# ElectromagnetArray_V01.net
KiCad netlist of a schematic drawn in EAGLE
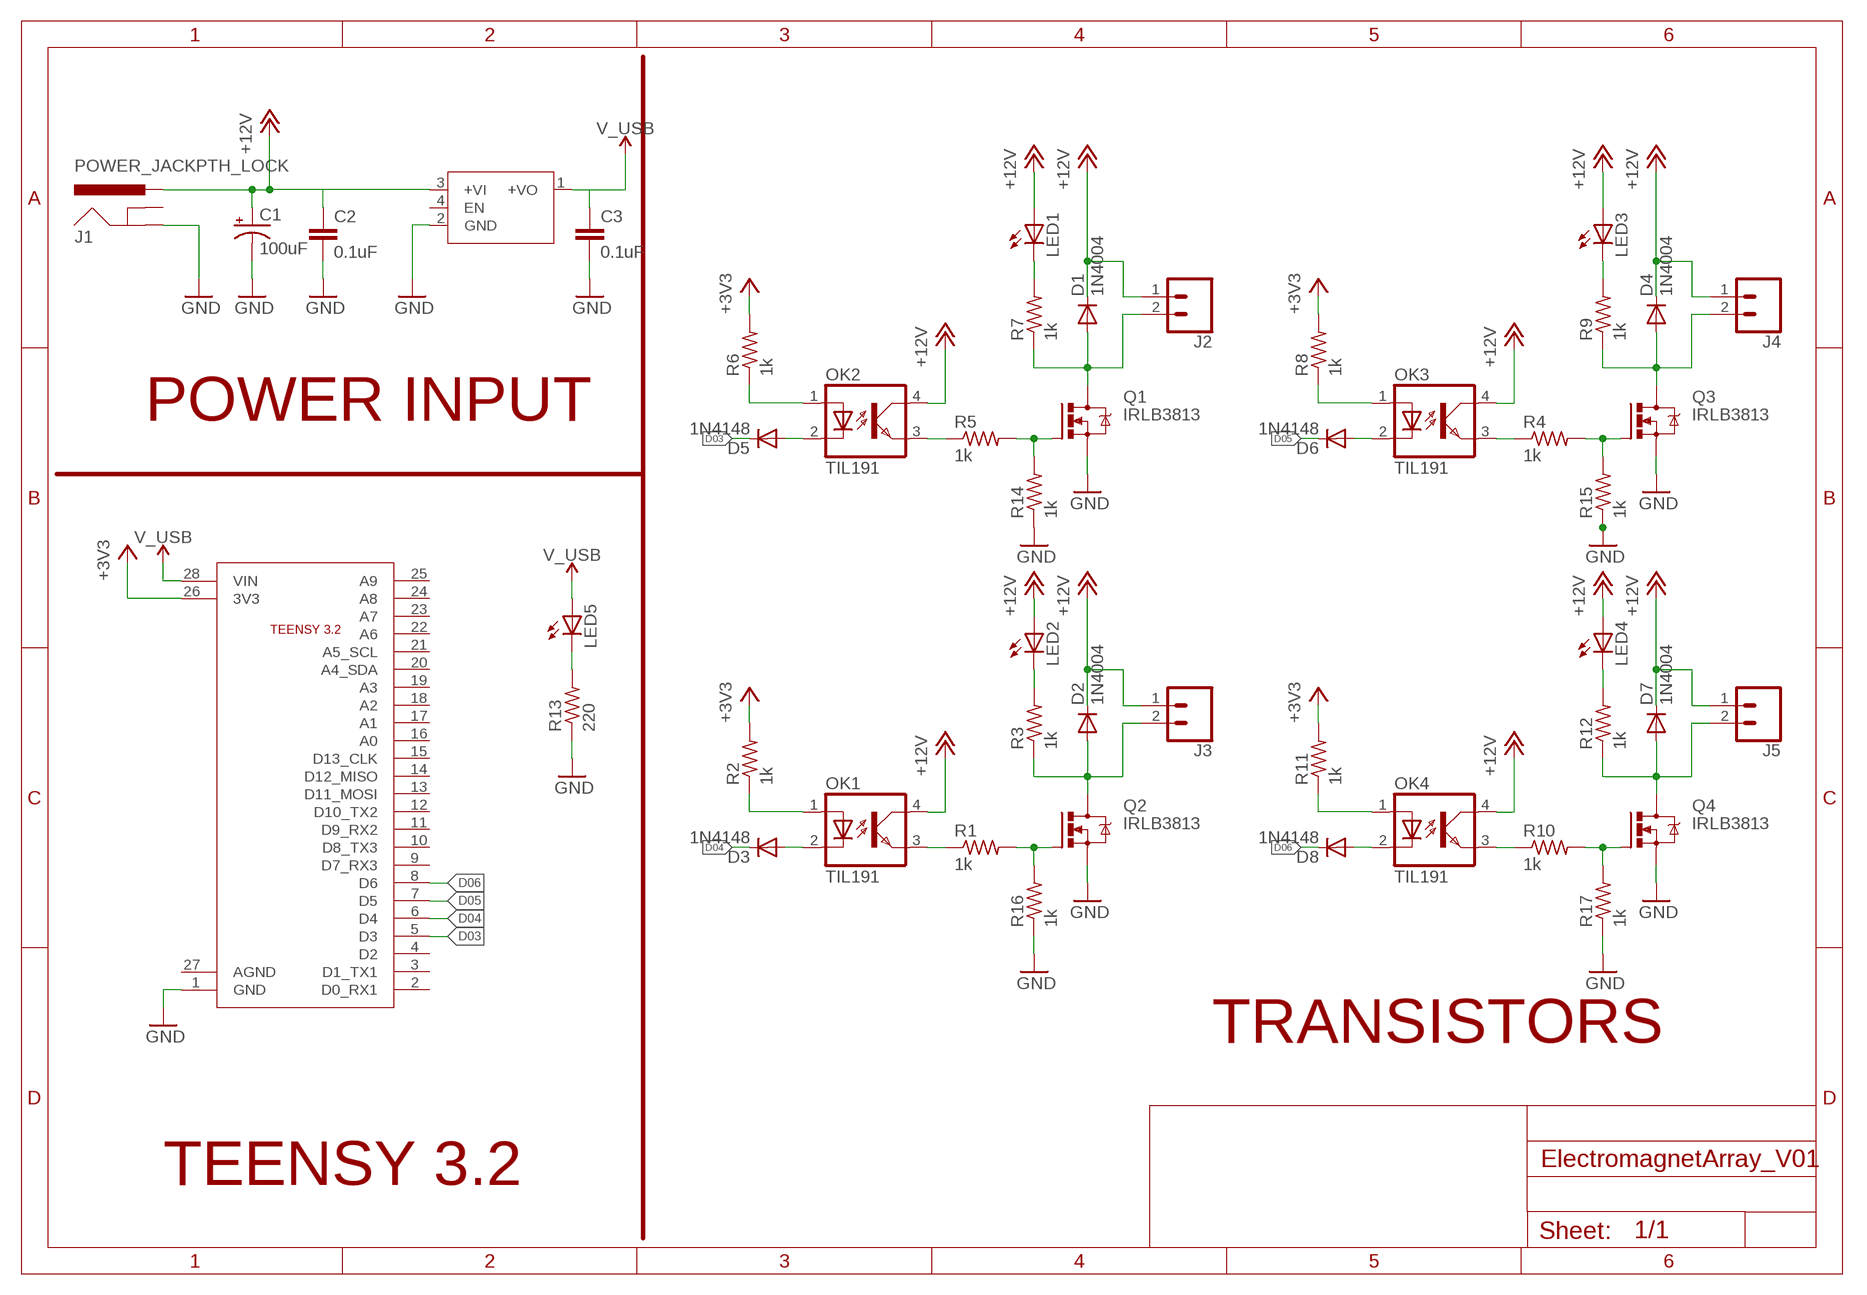
[diagram p0: schematic, sheet 1]

(export (version "E")
  (design (tool "Eeschema 10.0.6"))
  (components
    (comp (ref "C1")
      (value "100uF")
      (footprint "eagle-import:E3,5-8")
      (libsource (lib "eagle-import") (part "CPOL-USE3.5-8"))
    )
    (comp (ref "C2")
      (value "0.1uF")
      (footprint "eagle-import:C050-025X075")
      (libsource (lib "eagle-import") (part "C-EU050-025X075"))
    )
    (comp (ref "C3")
      (value "0.1uF")
      (footprint "eagle-import:C050-025X075")
      (libsource (lib "eagle-import") (part "C-EU050-025X075"))
    )
    (comp (ref "D1")
      (value "1N4004")
      (footprint "eagle-import:DO41-10")
      (libsource (lib "eagle-import") (part "1N4004"))
    )
    (comp (ref "D2")
      (value "1N4004")
      (footprint "eagle-import:DO41-10")
      (libsource (lib "eagle-import") (part "1N4004"))
    )
    (comp (ref "D3")
      (value "1N4148")
      (footprint "eagle-import:DO35-10")
      (libsource (lib "eagle-import") (part "1N4148DO35-10"))
    )
    (comp (ref "D4")
      (value "1N4004")
      (footprint "eagle-import:DO41-10")
      (libsource (lib "eagle-import") (part "1N4004"))
    )
    (comp (ref "D5")
      (value "1N4148")
      (footprint "eagle-import:DO35-10")
      (libsource (lib "eagle-import") (part "1N4148DO35-10"))
    )
    (comp (ref "D6")
      (value "1N4148")
      (footprint "eagle-import:DO35-10")
      (libsource (lib "eagle-import") (part "1N4148DO35-10"))
    )
    (comp (ref "D7")
      (value "1N4004")
      (footprint "eagle-import:DO41-10")
      (libsource (lib "eagle-import") (part "1N4004"))
    )
    (comp (ref "D8")
      (value "1N4148")
      (footprint "eagle-import:DO35-10")
      (libsource (lib "eagle-import") (part "1N4148DO35-10"))
    )
    (comp (ref "J1")
      (value "POWER_JACKPTH_LOCK")
      (footprint "eagle-import:POWER_JACK_PTH_LOCK")
      (libsource (lib "eagle-import") (part "POWER_JACKPTH_LOCK"))
    )
    (comp (ref "J2")
      (value "CONN_025MM")
      (footprint "eagle-import:SCREWTERMINAL-5MM-2")
      (libsource (lib "eagle-import") (part "CONN_025MM"))
    )
    (comp (ref "J3")
      (value "CONN_025MM")
      (footprint "eagle-import:SCREWTERMINAL-5MM-2")
      (libsource (lib "eagle-import") (part "CONN_025MM"))
    )
    (comp (ref "J4")
      (value "CONN_025MM")
      (footprint "eagle-import:SCREWTERMINAL-5MM-2")
      (libsource (lib "eagle-import") (part "CONN_025MM"))
    )
    (comp (ref "J5")
      (value "CONN_025MM")
      (footprint "eagle-import:SCREWTERMINAL-5MM-2")
      (libsource (lib "eagle-import") (part "CONN_025MM"))
    )
    (comp (ref "LED1")
      (value "LED5MM")
      (footprint "eagle-import:LED5MM")
      (libsource (lib "eagle-import") (part "LED5MM"))
    )
    (comp (ref "LED2")
      (value "LED5MM")
      (footprint "eagle-import:LED5MM")
      (libsource (lib "eagle-import") (part "LED5MM"))
    )
    (comp (ref "LED3")
      (value "LED5MM")
      (footprint "eagle-import:LED5MM")
      (libsource (lib "eagle-import") (part "LED5MM"))
    )
    (comp (ref "LED4")
      (value "LED5MM")
      (footprint "eagle-import:LED5MM")
      (libsource (lib "eagle-import") (part "LED5MM"))
    )
    (comp (ref "LED5")
      (value "LED5MM")
      (footprint "eagle-import:LED5MM")
      (libsource (lib "eagle-import") (part "LED5MM"))
    )
    (comp (ref "OK1")
      (value "TIL191")
      (footprint "eagle-import:DIL04")
      (libsource (lib "eagle-import") (part "TIL191"))
    )
    (comp (ref "OK2")
      (value "TIL191")
      (footprint "eagle-import:DIL04")
      (libsource (lib "eagle-import") (part "TIL191"))
    )
    (comp (ref "OK3")
      (value "TIL191")
      (footprint "eagle-import:DIL04")
      (libsource (lib "eagle-import") (part "TIL191"))
    )
    (comp (ref "OK4")
      (value "TIL191")
      (footprint "eagle-import:DIL04")
      (libsource (lib "eagle-import") (part "TIL191"))
    )
    (comp (ref "Q1")
      (value "IRLB3813")
      (footprint "eagle-import:TO220BV")
      (libsource (lib "eagle-import") (part "IRF740"))
    )
    (comp (ref "Q2")
      (value "IRLB3813")
      (footprint "eagle-import:TO220BV")
      (libsource (lib "eagle-import") (part "IRF740"))
    )
    (comp (ref "Q3")
      (value "IRLB3813")
      (footprint "eagle-import:TO220BV")
      (libsource (lib "eagle-import") (part "IRF740"))
    )
    (comp (ref "Q4")
      (value "IRLB3813")
      (footprint "eagle-import:TO220BV")
      (libsource (lib "eagle-import") (part "IRF740"))
    )
    (comp (ref "R1")
      (value "1k")
      (footprint "eagle-import:0204_7")
      (libsource (lib "eagle-import") (part "R-US_0204/7"))
    )
    (comp (ref "R2")
      (value "1k")
      (footprint "eagle-import:0204_7")
      (libsource (lib "eagle-import") (part "R-US_0204/7"))
    )
    (comp (ref "R3")
      (value "1k")
      (footprint "eagle-import:0204_7")
      (libsource (lib "eagle-import") (part "R-US_0204/7"))
    )
    (comp (ref "R4")
      (value "1k")
      (footprint "eagle-import:0204_7")
      (libsource (lib "eagle-import") (part "R-US_0204/7"))
    )
    (comp (ref "R5")
      (value "1k")
      (footprint "eagle-import:0204_7")
      (libsource (lib "eagle-import") (part "R-US_0204/7"))
    )
    (comp (ref "R6")
      (value "1k")
      (footprint "eagle-import:0204_7")
      (libsource (lib "eagle-import") (part "R-US_0204/7"))
    )
    (comp (ref "R7")
      (value "1k")
      (footprint "eagle-import:0204_7")
      (libsource (lib "eagle-import") (part "R-US_0204/7"))
    )
    (comp (ref "R8")
      (value "1k")
      (footprint "eagle-import:0204_7")
      (libsource (lib "eagle-import") (part "R-US_0204/7"))
    )
    (comp (ref "R9")
      (value "1k")
      (footprint "eagle-import:0204_7")
      (libsource (lib "eagle-import") (part "R-US_0204/7"))
    )
    (comp (ref "R10")
      (value "1k")
      (footprint "eagle-import:0204_7")
      (libsource (lib "eagle-import") (part "R-US_0204/7"))
    )
    (comp (ref "R11")
      (value "1k")
      (footprint "eagle-import:0204_7")
      (libsource (lib "eagle-import") (part "R-US_0204/7"))
    )
    (comp (ref "R12")
      (value "1k")
      (footprint "eagle-import:0204_7")
      (libsource (lib "eagle-import") (part "R-US_0204/7"))
    )
    (comp (ref "R13")
      (value "220")
      (footprint "eagle-import:0204_7")
      (libsource (lib "eagle-import") (part "R-US_0204/7"))
    )
    (comp (ref "R14")
      (value "1k")
      (footprint "eagle-import:0204_7")
      (libsource (lib "eagle-import") (part "R-US_0204/7"))
    )
    (comp (ref "R15")
      (value "1k")
      (footprint "eagle-import:0204_7")
      (libsource (lib "eagle-import") (part "R-US_0204/7"))
    )
    (comp (ref "R16")
      (value "1k")
      (footprint "eagle-import:0204_7")
      (libsource (lib "eagle-import") (part "R-US_0204/7"))
    )
    (comp (ref "R17")
      (value "1k")
      (footprint "eagle-import:0204_7")
      (libsource (lib "eagle-import") (part "R-US_0204/7"))
    )
    (comp (ref "U$1")
      (value "TEENSY3.2")
      (footprint "eagle-import:TEENSY")
      (libsource (lib "eagle-import") (part "TEENSY3.2"))
    )
    (comp (ref "U$2")
      (value "SMPS_SMALL")
      (footprint "eagle-import:SMPS_SMALL")
      (libsource (lib "eagle-import") (part "SMPS_SMALL"))
    )
  )
  (nets
    (net (code "1") (name "+3V3") (class "Default")
      (node (ref "R11") (pin "2") (pinfunction "2_2") (pintype "passive"))
      (node (ref "R2") (pin "2") (pinfunction "2_2") (pintype "passive"))
      (node (ref "R6") (pin "2") (pinfunction "2_2") (pintype "passive"))
      (node (ref "R8") (pin "2") (pinfunction "2_2") (pintype "passive"))
      (node (ref "U$1") (pin "26") (pinfunction "3V3_26") (pintype "bidirectional"))
    )
    (net (code "2") (name "+12V") (class "Default")
      (node (ref "C1") (pin "+") (pinfunction "+_+") (pintype "passive"))
      (node (ref "C2") (pin "1") (pinfunction "1_1") (pintype "passive"))
      (node (ref "D1") (pin "C") (pinfunction "C_C") (pintype "passive"))
      (node (ref "D2") (pin "C") (pinfunction "C_C") (pintype "passive"))
      (node (ref "D4") (pin "C") (pinfunction "C_C") (pintype "passive"))
      (node (ref "D7") (pin "C") (pinfunction "C_C") (pintype "passive"))
      (node (ref "J1") (pin "PWR") (pinfunction "PWR_PWR") (pintype "bidirectional"))
      (node (ref "J2") (pin "1") (pinfunction "1_1") (pintype "passive"))
      (node (ref "J3") (pin "1") (pinfunction "1_1") (pintype "passive"))
      (node (ref "J4") (pin "1") (pinfunction "1_1") (pintype "passive"))
      (node (ref "J5") (pin "1") (pinfunction "1_1") (pintype "passive"))
      (node (ref "LED1") (pin "A") (pinfunction "A_A") (pintype "passive"))
      (node (ref "LED2") (pin "A") (pinfunction "A_A") (pintype "passive"))
      (node (ref "LED3") (pin "A") (pinfunction "A_A") (pintype "passive"))
      (node (ref "LED4") (pin "A") (pinfunction "A_A") (pintype "passive"))
      (node (ref "OK1") (pin "4") (pinfunction "COL_4") (pintype "passive"))
      (node (ref "OK2") (pin "4") (pinfunction "COL_4") (pintype "passive"))
      (node (ref "OK3") (pin "4") (pinfunction "COL_4") (pintype "passive"))
      (node (ref "OK4") (pin "4") (pinfunction "COL_4") (pintype "passive"))
      (node (ref "U$2") (pin "3") (pinfunction "+VI_3") (pintype "bidirectional"))
    )
    (net (code "3") (name "D03") (class "Default")
      (node (ref "D5") (pin "C") (pinfunction "C_C") (pintype "passive"))
      (node (ref "U$1") (pin "5") (pinfunction "D3_5") (pintype "bidirectional"))
    )
    (net (code "4") (name "D04") (class "Default")
      (node (ref "D3") (pin "C") (pinfunction "C_C") (pintype "passive"))
      (node (ref "U$1") (pin "6") (pinfunction "D4_6") (pintype "bidirectional"))
    )
    (net (code "5") (name "D05") (class "Default")
      (node (ref "D6") (pin "C") (pinfunction "C_C") (pintype "passive"))
      (node (ref "U$1") (pin "7") (pinfunction "D5_7") (pintype "bidirectional"))
    )
    (net (code "6") (name "D06") (class "Default")
      (node (ref "D8") (pin "C") (pinfunction "C_C") (pintype "passive"))
      (node (ref "U$1") (pin "8") (pinfunction "D6_8") (pintype "bidirectional"))
    )
    (net (code "7") (name "GND") (class "Default")
      (node (ref "C1") (pin "-") (pinfunction "-_-") (pintype "passive"))
      (node (ref "C2") (pin "2") (pinfunction "2_2") (pintype "passive"))
      (node (ref "C3") (pin "2") (pinfunction "2_2") (pintype "passive"))
      (node (ref "J1") (pin "GND") (pinfunction "GND_GND") (pintype "bidirectional"))
      (node (ref "Q1") (pin "S") (pinfunction "S_S") (pintype "passive"))
      (node (ref "Q2") (pin "S") (pinfunction "S_S") (pintype "passive"))
      (node (ref "Q3") (pin "S") (pinfunction "S_S") (pintype "passive"))
      (node (ref "Q4") (pin "S") (pinfunction "S_S") (pintype "passive"))
      (node (ref "R13") (pin "1") (pinfunction "1_1") (pintype "passive"))
      (node (ref "R14") (pin "1") (pinfunction "1_1") (pintype "passive"))
      (node (ref "R15") (pin "1") (pinfunction "1_1") (pintype "passive"))
      (node (ref "R16") (pin "1") (pinfunction "1_1") (pintype "passive"))
      (node (ref "R17") (pin "1") (pinfunction "1_1") (pintype "passive"))
      (node (ref "U$1") (pin "1") (pinfunction "GND_1") (pintype "bidirectional"))
      (node (ref "U$2") (pin "2") (pinfunction "GND_2") (pintype "bidirectional"))
    )
    (net (code "8") (name "Net-(D1-PadA)") (class "Default")
      (node (ref "D1") (pin "A") (pinfunction "A_A") (pintype "passive"))
      (node (ref "J2") (pin "2") (pinfunction "2_2") (pintype "passive"))
      (node (ref "Q1") (pin "D") (pinfunction "D_D") (pintype "passive"))
      (node (ref "R7") (pin "1") (pinfunction "1_1") (pintype "passive"))
    )
    (net (code "9") (name "Net-(D2-PadA)") (class "Default")
      (node (ref "D2") (pin "A") (pinfunction "A_A") (pintype "passive"))
      (node (ref "J3") (pin "2") (pinfunction "2_2") (pintype "passive"))
      (node (ref "Q2") (pin "D") (pinfunction "D_D") (pintype "passive"))
      (node (ref "R3") (pin "1") (pinfunction "1_1") (pintype "passive"))
    )
    (net (code "10") (name "Net-(D4-PadA)") (class "Default")
      (node (ref "D4") (pin "A") (pinfunction "A_A") (pintype "passive"))
      (node (ref "J4") (pin "2") (pinfunction "2_2") (pintype "passive"))
      (node (ref "Q3") (pin "D") (pinfunction "D_D") (pintype "passive"))
      (node (ref "R9") (pin "1") (pinfunction "1_1") (pintype "passive"))
    )
    (net (code "11") (name "Net-(D7-PadA)") (class "Default")
      (node (ref "D7") (pin "A") (pinfunction "A_A") (pintype "passive"))
      (node (ref "J5") (pin "2") (pinfunction "2_2") (pintype "passive"))
      (node (ref "Q4") (pin "D") (pinfunction "D_D") (pintype "passive"))
      (node (ref "R12") (pin "1") (pinfunction "1_1") (pintype "passive"))
    )
    (net (code "12") (name "Net-(LED1-C)") (class "Default")
      (node (ref "LED1") (pin "K") (pinfunction "C_K") (pintype "passive"))
      (node (ref "R7") (pin "2") (pinfunction "2_2") (pintype "passive"))
    )
    (net (code "13") (name "Net-(LED2-C)") (class "Default")
      (node (ref "LED2") (pin "K") (pinfunction "C_K") (pintype "passive"))
      (node (ref "R3") (pin "2") (pinfunction "2_2") (pintype "passive"))
    )
    (net (code "14") (name "Net-(LED3-C)") (class "Default")
      (node (ref "LED3") (pin "K") (pinfunction "C_K") (pintype "passive"))
      (node (ref "R9") (pin "2") (pinfunction "2_2") (pintype "passive"))
    )
    (net (code "15") (name "Net-(LED4-C)") (class "Default")
      (node (ref "LED4") (pin "K") (pinfunction "C_K") (pintype "passive"))
      (node (ref "R12") (pin "2") (pinfunction "2_2") (pintype "passive"))
    )
    (net (code "16") (name "Net-(LED5-C)") (class "Default")
      (node (ref "LED5") (pin "K") (pinfunction "C_K") (pintype "passive"))
      (node (ref "R13") (pin "2") (pinfunction "2_2") (pintype "passive"))
    )
    (net (code "17") (name "Net-(OK1-A)") (class "Default")
      (node (ref "OK1") (pin "1") (pinfunction "A_1") (pintype "passive"))
      (node (ref "R2") (pin "1") (pinfunction "1_1") (pintype "passive"))
    )
    (net (code "18") (name "Net-(OK1-C)") (class "Default")
      (node (ref "D3") (pin "A") (pinfunction "A_A") (pintype "passive"))
      (node (ref "OK1") (pin "2") (pinfunction "C_2") (pintype "passive"))
    )
    (net (code "19") (name "Net-(OK1-EMIT)") (class "Default")
      (node (ref "OK1") (pin "3") (pinfunction "EMIT_3") (pintype "passive"))
      (node (ref "R1") (pin "1") (pinfunction "1_1") (pintype "passive"))
    )
    (net (code "20") (name "Net-(OK2-A)") (class "Default")
      (node (ref "OK2") (pin "1") (pinfunction "A_1") (pintype "passive"))
      (node (ref "R6") (pin "1") (pinfunction "1_1") (pintype "passive"))
    )
    (net (code "21") (name "Net-(OK2-C)") (class "Default")
      (node (ref "D5") (pin "A") (pinfunction "A_A") (pintype "passive"))
      (node (ref "OK2") (pin "2") (pinfunction "C_2") (pintype "passive"))
    )
    (net (code "22") (name "Net-(OK2-EMIT)") (class "Default")
      (node (ref "OK2") (pin "3") (pinfunction "EMIT_3") (pintype "passive"))
      (node (ref "R5") (pin "1") (pinfunction "1_1") (pintype "passive"))
    )
    (net (code "23") (name "Net-(OK3-A)") (class "Default")
      (node (ref "OK3") (pin "1") (pinfunction "A_1") (pintype "passive"))
      (node (ref "R8") (pin "1") (pinfunction "1_1") (pintype "passive"))
    )
    (net (code "24") (name "Net-(OK3-C)") (class "Default")
      (node (ref "D6") (pin "A") (pinfunction "A_A") (pintype "passive"))
      (node (ref "OK3") (pin "2") (pinfunction "C_2") (pintype "passive"))
    )
    (net (code "25") (name "Net-(OK3-EMIT)") (class "Default")
      (node (ref "OK3") (pin "3") (pinfunction "EMIT_3") (pintype "passive"))
      (node (ref "R4") (pin "1") (pinfunction "1_1") (pintype "passive"))
    )
    (net (code "26") (name "Net-(OK4-A)") (class "Default")
      (node (ref "OK4") (pin "1") (pinfunction "A_1") (pintype "passive"))
      (node (ref "R11") (pin "1") (pinfunction "1_1") (pintype "passive"))
    )
    (net (code "27") (name "Net-(OK4-C)") (class "Default")
      (node (ref "D8") (pin "A") (pinfunction "A_A") (pintype "passive"))
      (node (ref "OK4") (pin "2") (pinfunction "C_2") (pintype "passive"))
    )
    (net (code "28") (name "Net-(OK4-EMIT)") (class "Default")
      (node (ref "OK4") (pin "3") (pinfunction "EMIT_3") (pintype "passive"))
      (node (ref "R10") (pin "1") (pinfunction "1_1") (pintype "passive"))
    )
    (net (code "29") (name "Net-(Q1-PadG)") (class "Default")
      (node (ref "Q1") (pin "G") (pinfunction "G_G") (pintype "passive"))
      (node (ref "R14") (pin "2") (pinfunction "2_2") (pintype "passive"))
      (node (ref "R5") (pin "2") (pinfunction "2_2") (pintype "passive"))
    )
    (net (code "30") (name "Net-(Q2-PadG)") (class "Default")
      (node (ref "Q2") (pin "G") (pinfunction "G_G") (pintype "passive"))
      (node (ref "R1") (pin "2") (pinfunction "2_2") (pintype "passive"))
      (node (ref "R16") (pin "2") (pinfunction "2_2") (pintype "passive"))
    )
    (net (code "31") (name "Net-(Q3-PadG)") (class "Default")
      (node (ref "Q3") (pin "G") (pinfunction "G_G") (pintype "passive"))
      (node (ref "R15") (pin "2") (pinfunction "2_2") (pintype "passive"))
      (node (ref "R4") (pin "2") (pinfunction "2_2") (pintype "passive"))
    )
    (net (code "32") (name "Net-(Q4-PadG)") (class "Default")
      (node (ref "Q4") (pin "G") (pinfunction "G_G") (pintype "passive"))
      (node (ref "R10") (pin "2") (pinfunction "2_2") (pintype "passive"))
      (node (ref "R17") (pin "2") (pinfunction "2_2") (pintype "passive"))
    )
    (net (code "33") (name "V_USB") (class "Default")
      (node (ref "C3") (pin "1") (pinfunction "1_1") (pintype "passive"))
      (node (ref "LED5") (pin "A") (pinfunction "A_A") (pintype "passive"))
      (node (ref "U$1") (pin "28") (pinfunction "VIN_28") (pintype "bidirectional"))
      (node (ref "U$2") (pin "1") (pinfunction "+VO_1") (pintype "bidirectional"))
    )
    (net (code "34") (name "unconnected-(J1-PadGNDBREAK)") (class "Default")
      (node (ref "J1") (pin "GNDBREAK") (pinfunction "GNDBREAK_GNDBREAK") (pintype "bidirectional"))
    )
    (net (code "35") (name "unconnected-(U$1-A0-Pad16)") (class "Default")
      (node (ref "U$1") (pin "16") (pinfunction "A0_16") (pintype "bidirectional"))
    )
    (net (code "36") (name "unconnected-(U$1-A1-Pad17)") (class "Default")
      (node (ref "U$1") (pin "17") (pinfunction "A1_17") (pintype "bidirectional"))
    )
    (net (code "37") (name "unconnected-(U$1-A2-Pad18)") (class "Default")
      (node (ref "U$1") (pin "18") (pinfunction "A2_18") (pintype "bidirectional"))
    )
    (net (code "38") (name "unconnected-(U$1-A3-Pad19)") (class "Default")
      (node (ref "U$1") (pin "19") (pinfunction "A3_19") (pintype "bidirectional"))
    )
    (net (code "39") (name "unconnected-(U$1-A4_SDA-Pad20)") (class "Default")
      (node (ref "U$1") (pin "20") (pinfunction "A4_SDA_20") (pintype "bidirectional"))
    )
    (net (code "40") (name "unconnected-(U$1-A5_SCL-Pad21)") (class "Default")
      (node (ref "U$1") (pin "21") (pinfunction "A5_SCL_21") (pintype "bidirectional"))
    )
    (net (code "41") (name "unconnected-(U$1-A6-Pad22)") (class "Default")
      (node (ref "U$1") (pin "22") (pinfunction "A6_22") (pintype "bidirectional"))
    )
    (net (code "42") (name "unconnected-(U$1-A7-Pad23)") (class "Default")
      (node (ref "U$1") (pin "23") (pinfunction "A7_23") (pintype "bidirectional"))
    )
    (net (code "43") (name "unconnected-(U$1-A8-Pad24)") (class "Default")
      (node (ref "U$1") (pin "24") (pinfunction "A8_24") (pintype "bidirectional"))
    )
    (net (code "44") (name "unconnected-(U$1-A9-Pad25)") (class "Default")
      (node (ref "U$1") (pin "25") (pinfunction "A9_25") (pintype "bidirectional"))
    )
    (net (code "45") (name "unconnected-(U$1-AGND-Pad27)") (class "Default")
      (node (ref "U$1") (pin "27") (pinfunction "AGND_27") (pintype "bidirectional"))
    )
    (net (code "46") (name "unconnected-(U$1-D0_RX1-Pad2)") (class "Default")
      (node (ref "U$1") (pin "2") (pinfunction "D0_RX1_2") (pintype "bidirectional"))
    )
    (net (code "47") (name "unconnected-(U$1-D1_TX1-Pad3)") (class "Default")
      (node (ref "U$1") (pin "3") (pinfunction "D1_TX1_3") (pintype "bidirectional"))
    )
    (net (code "48") (name "unconnected-(U$1-D2-Pad4)") (class "Default")
      (node (ref "U$1") (pin "4") (pinfunction "D2_4") (pintype "bidirectional"))
    )
    (net (code "49") (name "unconnected-(U$1-D7_RX3-Pad9)") (class "Default")
      (node (ref "U$1") (pin "9") (pinfunction "D7_RX3_9") (pintype "bidirectional"))
    )
    (net (code "50") (name "unconnected-(U$1-D8_TX3-Pad10)") (class "Default")
      (node (ref "U$1") (pin "10") (pinfunction "D8_TX3_10") (pintype "bidirectional"))
    )
    (net (code "51") (name "unconnected-(U$1-D9_RX2-Pad11)") (class "Default")
      (node (ref "U$1") (pin "11") (pinfunction "D9_RX2_11") (pintype "bidirectional"))
    )
    (net (code "52") (name "unconnected-(U$1-D10_TX2-Pad12)") (class "Default")
      (node (ref "U$1") (pin "12") (pinfunction "D10_TX2_12") (pintype "bidirectional"))
    )
    (net (code "53") (name "unconnected-(U$1-D11_MOSI-Pad13)") (class "Default")
      (node (ref "U$1") (pin "13") (pinfunction "D11_MOSI_13") (pintype "bidirectional"))
    )
    (net (code "54") (name "unconnected-(U$1-D12_MISO-Pad14)") (class "Default")
      (node (ref "U$1") (pin "14") (pinfunction "D12_MISO_14") (pintype "bidirectional"))
    )
    (net (code "55") (name "unconnected-(U$1-D13_CLK-Pad15)") (class "Default")
      (node (ref "U$1") (pin "15") (pinfunction "D13_CLK_15") (pintype "bidirectional"))
    )
    (net (code "56") (name "unconnected-(U$2-EN-Pad4)") (class "Default")
      (node (ref "U$2") (pin "4") (pinfunction "EN_4") (pintype "bidirectional"))
    )
  )
)
